# Top.net
KiCad netlist of a schematic drawn in Altium Designer
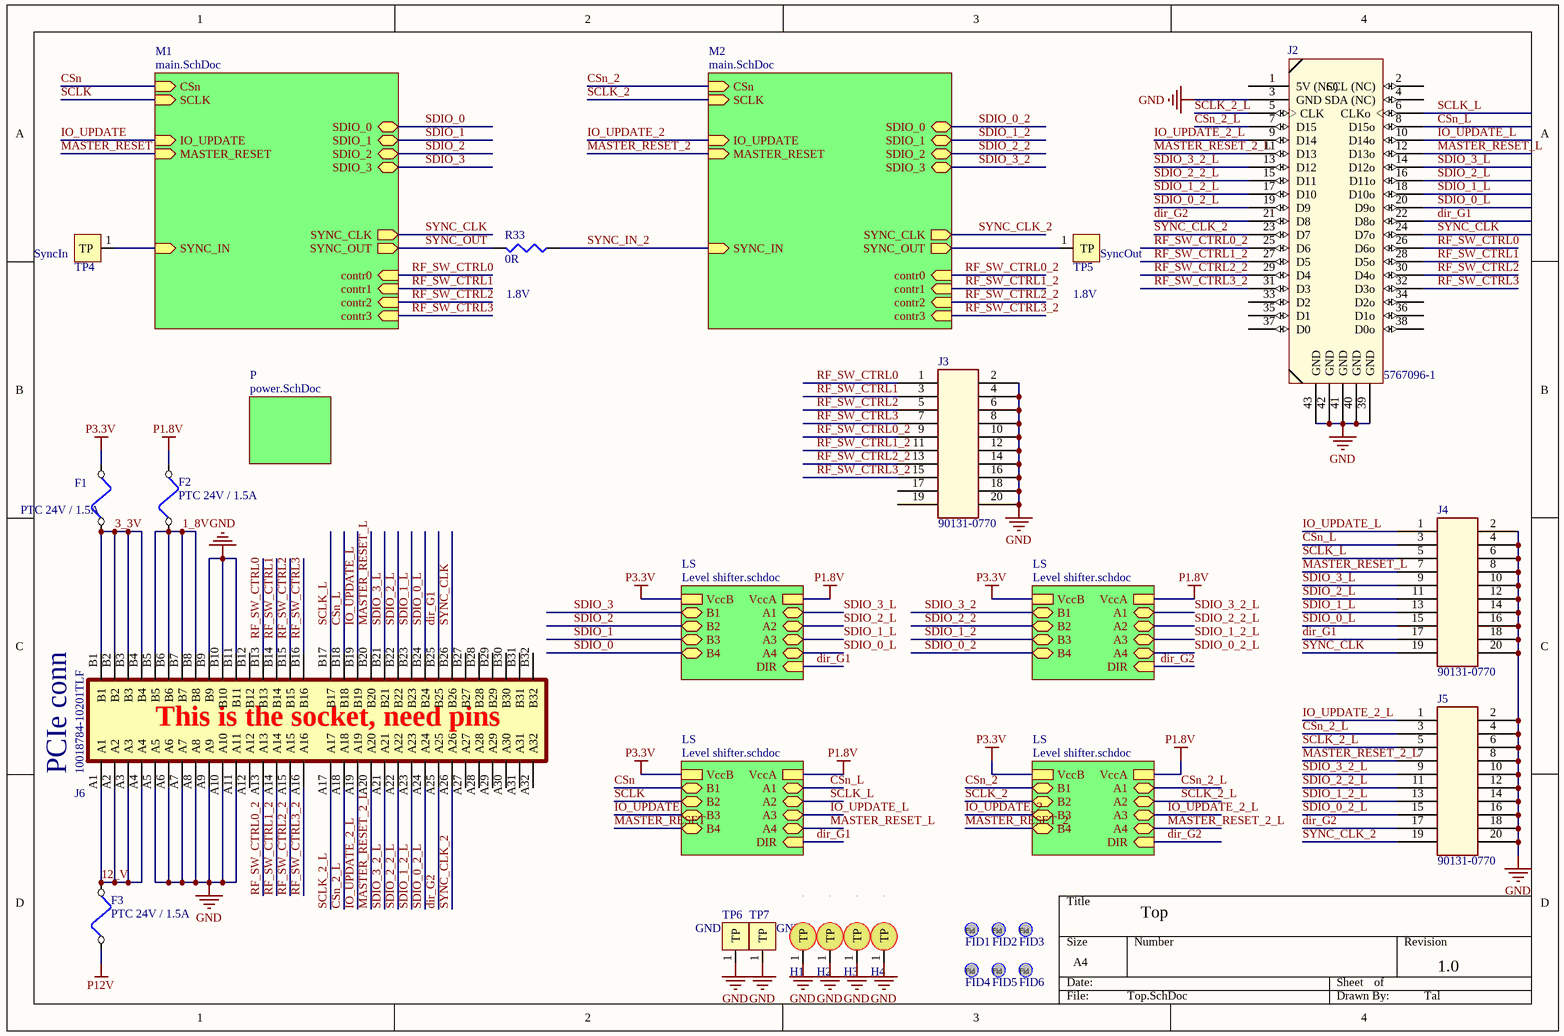
[diagram p0: Top.SchDoc]

(export (version "E")
  (design (tool "Eeschema 10.0.6"))
  (components
    (comp (ref "F1")
      (value "PTC 24V / 1.5A")
      (footprint "Landa_PCB:1812_F")
      (description "FUSE PTC 24V 1.5A POLYFUSE 1812")
      (fields
        (field (name "MANUFACTURER") "Littelfuse Inc")
        (field (name "MANUFACTURER PART NUMBER") "1812L150/24MR")
      )
      (libsource (lib "DPB_spliter") (part "1812L150/24MR"))
    )
    (comp (ref "F2")
      (value "PTC 24V / 1.5A")
      (footprint "Landa_PCB:1812_F")
      (description "FUSE PTC 24V 1.5A POLYFUSE 1812")
      (fields
        (field (name "MANUFACTURER") "Littelfuse Inc")
        (field (name "MANUFACTURER PART NUMBER") "1812L150/24MR")
      )
      (libsource (lib "DPB_spliter") (part "1812L150/24MR"))
    )
    (comp (ref "F3")
      (value "PTC 24V / 1.5A")
      (footprint "Landa_PCB:1812_F")
      (description "FUSE PTC 24V 1.5A POLYFUSE 1812")
      (fields
        (field (name "MANUFACTURER") "Littelfuse Inc")
        (field (name "MANUFACTURER PART NUMBER") "1812L150/24MR")
      )
      (libsource (lib "DPB_spliter") (part "1812L150/24MR"))
    )
    (comp (ref "FID1")
      (value "Fiducial")
      (footprint "Fiducial")
      (libsource (lib "DDS_PCB") (part "Fiducial"))
    )
    (comp (ref "FID2")
      (value "Fiducial")
      (footprint "Fiducial")
      (libsource (lib "DDS_PCB") (part "Fiducial"))
    )
    (comp (ref "FID3")
      (value "Fiducial")
      (footprint "Fiducial")
      (libsource (lib "DDS_PCB") (part "Fiducial"))
    )
    (comp (ref "FID4")
      (value "Fiducial")
      (footprint "Fiducial")
      (libsource (lib "DDS_PCB") (part "Fiducial"))
    )
    (comp (ref "FID5")
      (value "Fiducial")
      (footprint "Fiducial")
      (libsource (lib "DDS_PCB") (part "Fiducial"))
    )
    (comp (ref "FID6")
      (value "Fiducial")
      (footprint "Fiducial")
      (libsource (lib "DDS_PCB") (part "Fiducial"))
    )
    (comp (ref "H1")
      (value "Hole 3mm")
      (footprint "hole 3mm")
      (description "hole 3mm")
      (libsource (lib "L_SCH_Misc") (part "Hole 3mm"))
    )
    (comp (ref "H2")
      (value "Hole 3mm")
      (footprint "hole 3mm")
      (description "hole 3mm")
      (libsource (lib "L_SCH_Misc") (part "Hole 3mm"))
    )
    (comp (ref "H3")
      (value "Hole 3mm")
      (footprint "hole 3mm")
      (description "hole 3mm")
      (libsource (lib "L_SCH_Misc") (part "Hole 3mm"))
    )
    (comp (ref "H4")
      (value "Hole 3mm")
      (footprint "hole 3mm")
      (description "hole 3mm")
      (libsource (lib "L_SCH_Misc") (part "Hole 3mm"))
    )
    (comp (ref "J2")
      (value "5767096-1")
      (footprint "MICTOR-38_PIN")
      (description "CONN MICTOR 38POS .025 VERT SMD")
      (fields
        (field (name "MANUFACTURER") "TE Connectivity")
        (field (name "MANUFACTURER PART NUMBER") "5767096-1")
      )
      (libsource (lib "L_SCH_J_Z") (part "5767096-1"))
    )
    (comp (ref "J3")
      (value "90131-0770")
      (footprint "HEADER_10x2")
      (description "CONN HEADER 20 TH")
      (fields
        (field (name "MANUFACTURER") "Molex Connector Corporation")
        (field (name "MANUFACTURER PART NUMBER") "90131-0770")
      )
      (libsource (lib "L_SCH_J_Z") (part "90131-0770"))
    )
    (comp (ref "J4")
      (value "90131-0770")
      (footprint "HEADER_10x2")
      (description "CONN HEADER 20 TH")
      (fields
        (field (name "MANUFACTURER") "Molex Connector Corporation")
        (field (name "MANUFACTURER PART NUMBER") "90131-0770")
      )
      (libsource (lib "L_SCH_J_Z") (part "90131-0770"))
    )
    (comp (ref "J5")
      (value "90131-0770")
      (footprint "HEADER_10x2")
      (description "CONN HEADER 20 TH")
      (fields
        (field (name "MANUFACTURER") "Molex Connector Corporation")
        (field (name "MANUFACTURER PART NUMBER") "90131-0770")
      )
      (libsource (lib "L_SCH_J_Z") (part "90131-0770"))
    )
    (comp (ref "J6")
      (value "10018784-10201TLF")
      (footprint "PCIE_8LANE_EDGE")
      (description "64 Position Female Connector PCI Expressâ„¢ Gold 0.039 _1.00mm_ Black")
      (fields (field (name "MF") "Amphenol ICC"))
      (libsource (lib "10018784-10201TLF") (part "10018784-10201TLF"))
    )
    (comp (ref "R33")
      (value "0R")
      (footprint "R0402")
      (description "RES 0 OHM 1/10W 1% 0402 SMD")
      (fields
        (field (name "MANUFACTURER PART NUMBER") "ERJ-2RKF1000X")
        (field (name "MANUFACTURER") "Panasonic Electronic Components")
      )
      (libsource (lib "L_SCH_R") (part "RES 100 OHM 1/10W 1% 0402 SMD"))
    )
    (comp (ref "TP4")
      (value "SyncIn")
      (footprint "Landa_PCB:TP_2x1.8")
      (description "TP PC MINIATURE SMT")
      (fields
        (field (name "MANUFACTURER") "Keystone Electronics")
        (field (name "MANUFACTURER PART NUMBER") "5015")
      )
      (libsource (lib "DPB_spliter") (part "TP mini_2"))
    )
    (comp (ref "TP5")
      (value "SyncOut")
      (footprint "Landa_PCB:TP_2x1.8")
      (description "TP PC MINIATURE SMT")
      (fields
        (field (name "MANUFACTURER") "Keystone Electronics")
        (field (name "MANUFACTURER PART NUMBER") "5015")
      )
      (libsource (lib "") (part "TP mini_2_2"))
    )
    (comp (ref "TP6")
      (value "GND")
      (footprint "Landa_PCB:TP_2x1.8")
      (description "TP PC MINIATURE SMT")
      (fields
        (field (name "MANUFACTURER") "Keystone Electronics")
        (field (name "MANUFACTURER PART NUMBER") "5015")
      )
      (libsource (lib "") (part "TP mini_2_1"))
    )
    (comp (ref "TP7")
      (value "GND")
      (footprint "Landa_PCB:TP_2x1.8")
      (description "TP PC MINIATURE SMT")
      (fields
        (field (name "MANUFACTURER") "Keystone Electronics")
        (field (name "MANUFACTURER PART NUMBER") "5015")
      )
      (libsource (lib "DPB_spliter") (part "TP mini_1"))
    )
  )
  (nets
    (net (code "1") (name "/1_8V") (class "Default")
      (node (ref "F2") (pin "1") (pinfunction "1_1") (pintype "passive"))
      (node (ref "J6") (pin "B5") (pinfunction "B5_B5") (pintype "passive"))
      (node (ref "J6") (pin "B6") (pinfunction "B6_B6") (pintype "passive"))
      (node (ref "J6") (pin "B7") (pinfunction "B7_B7") (pintype "passive"))
      (node (ref "J6") (pin "B8") (pinfunction "B8_B8") (pintype "passive"))
    )
    (net (code "2") (name "/3_3V") (class "Default")
      (node (ref "F1") (pin "1") (pinfunction "1_1") (pintype "passive"))
      (node (ref "J6") (pin "B1") (pinfunction "B1_B1") (pintype "passive"))
      (node (ref "J6") (pin "B2") (pinfunction "B2_B2") (pintype "passive"))
      (node (ref "J6") (pin "B3") (pinfunction "B3_B3") (pintype "passive"))
      (node (ref "J6") (pin "B4") (pinfunction "B4_B4") (pintype "passive"))
    )
    (net (code "3") (name "/12_V") (class "Default")
      (node (ref "F3") (pin "2") (pinfunction "2_2") (pintype "passive"))
      (node (ref "J6") (pin "A1") (pinfunction "A1_A1") (pintype "passive"))
      (node (ref "J6") (pin "A2") (pinfunction "A2_A2") (pintype "passive"))
      (node (ref "J6") (pin "A3") (pinfunction "A3_A3") (pintype "passive"))
      (node (ref "J6") (pin "A4") (pinfunction "A4_A4") (pintype "passive"))
    )
    (net (code "6") (name "/CSn_2_L") (class "Default")
      (node (ref "J2") (pin "7") (pinfunction "D15_7") (pintype "bidirectional"))
      (node (ref "J5") (pin "3") (pinfunction "3_3") (pintype "passive"))
      (node (ref "J6") (pin "A18") (pinfunction "A18_A18") (pintype "passive"))
    )
    (net (code "7") (name "/CSn_L") (class "Default")
      (node (ref "J2") (pin "8") (pinfunction "D15o_8") (pintype "bidirectional"))
      (node (ref "J4") (pin "3") (pinfunction "3_3") (pintype "passive"))
      (node (ref "J6") (pin "B18") (pinfunction "B18_B18") (pintype "passive"))
    )
    (net (code "10") (name "/IO_UPDATE_2_L") (class "Default")
      (node (ref "J2") (pin "9") (pinfunction "D14_9") (pintype "bidirectional"))
      (node (ref "J5") (pin "1") (pinfunction "1_1") (pintype "passive"))
      (node (ref "J6") (pin "A19") (pinfunction "A19_A19") (pintype "passive"))
    )
    (net (code "11") (name "/IO_UPDATE_L") (class "Default")
      (node (ref "J2") (pin "10") (pinfunction "D14o_10") (pintype "bidirectional"))
      (node (ref "J4") (pin "1") (pinfunction "1_1") (pintype "passive"))
      (node (ref "J6") (pin "B19") (pinfunction "B19_B19") (pintype "passive"))
    )
    (net (code "14") (name "/MASTER_RESET_2_L") (class "Default")
      (node (ref "J2") (pin "11") (pinfunction "D13_11") (pintype "bidirectional"))
      (node (ref "J5") (pin "7") (pinfunction "7_7") (pintype "passive"))
      (node (ref "J6") (pin "A20") (pinfunction "A20_A20") (pintype "passive"))
    )
    (net (code "15") (name "/MASTER_RESET_L") (class "Default")
      (node (ref "J2") (pin "12") (pinfunction "D13o_12") (pintype "bidirectional"))
      (node (ref "J4") (pin "7") (pinfunction "7_7") (pintype "passive"))
      (node (ref "J6") (pin "B20") (pinfunction "B20_B20") (pintype "passive"))
    )
    (net (code "16") (name "/RF_SW_CTRL0") (class "Default")
      (node (ref "J2") (pin "26") (pinfunction "D6o_26") (pintype "bidirectional"))
      (node (ref "J3") (pin "1") (pinfunction "1_1") (pintype "passive"))
      (node (ref "J6") (pin "B13") (pinfunction "B13_B13") (pintype "passive"))
    )
    (net (code "17") (name "/RF_SW_CTRL0_2") (class "Default")
      (node (ref "J2") (pin "25") (pinfunction "D6_25") (pintype "bidirectional"))
      (node (ref "J3") (pin "9") (pinfunction "9_9") (pintype "passive"))
      (node (ref "J6") (pin "A13") (pinfunction "A13_A13") (pintype "passive"))
    )
    (net (code "18") (name "/RF_SW_CTRL1") (class "Default")
      (node (ref "J2") (pin "28") (pinfunction "D5o_28") (pintype "bidirectional"))
      (node (ref "J3") (pin "3") (pinfunction "3_3") (pintype "passive"))
      (node (ref "J6") (pin "B14") (pinfunction "B14_B14") (pintype "passive"))
    )
    (net (code "19") (name "/RF_SW_CTRL1_2") (class "Default")
      (node (ref "J2") (pin "27") (pinfunction "D5_27") (pintype "bidirectional"))
      (node (ref "J3") (pin "11") (pinfunction "11_11") (pintype "passive"))
      (node (ref "J6") (pin "A14") (pinfunction "A14_A14") (pintype "passive"))
    )
    (net (code "20") (name "/RF_SW_CTRL2") (class "Default")
      (node (ref "J2") (pin "30") (pinfunction "D4o_30") (pintype "bidirectional"))
      (node (ref "J3") (pin "5") (pinfunction "5_5") (pintype "passive"))
      (node (ref "J6") (pin "B15") (pinfunction "B15_B15") (pintype "passive"))
    )
    (net (code "21") (name "/RF_SW_CTRL2_2") (class "Default")
      (node (ref "J2") (pin "29") (pinfunction "D4_29") (pintype "bidirectional"))
      (node (ref "J3") (pin "13") (pinfunction "13_13") (pintype "passive"))
      (node (ref "J6") (pin "A15") (pinfunction "A15_A15") (pintype "passive"))
    )
    (net (code "22") (name "/RF_SW_CTRL3") (class "Default")
      (node (ref "J2") (pin "32") (pinfunction "D3o_32") (pintype "bidirectional"))
      (node (ref "J3") (pin "7") (pinfunction "7_7") (pintype "passive"))
      (node (ref "J6") (pin "B16") (pinfunction "B16_B16") (pintype "passive"))
    )
    (net (code "23") (name "/RF_SW_CTRL3_2") (class "Default")
      (node (ref "J2") (pin "31") (pinfunction "D3_31") (pintype "bidirectional"))
      (node (ref "J3") (pin "15") (pinfunction "15_15") (pintype "passive"))
      (node (ref "J6") (pin "A16") (pinfunction "A16_A16") (pintype "passive"))
    )
    (net (code "26") (name "/SCLK_2_L") (class "Default")
      (node (ref "J2") (pin "5") (pinfunction "CLK_5") (pintype "bidirectional"))
      (node (ref "J5") (pin "5") (pinfunction "5_5") (pintype "passive"))
      (node (ref "J6") (pin "A17") (pinfunction "A17_A17") (pintype "passive"))
    )
    (net (code "27") (name "/SCLK_L") (class "Default")
      (node (ref "J2") (pin "6") (pinfunction "CLKo_6") (pintype "bidirectional"))
      (node (ref "J4") (pin "5") (pinfunction "5_5") (pintype "passive"))
      (node (ref "J6") (pin "B17") (pinfunction "B17_B17") (pintype "passive"))
    )
    (net (code "30") (name "/SDIO_0_2_L") (class "Default")
      (node (ref "J2") (pin "19") (pinfunction "D9_19") (pintype "bidirectional"))
      (node (ref "J5") (pin "15") (pinfunction "15_15") (pintype "passive"))
      (node (ref "J6") (pin "A24") (pinfunction "A24_A24") (pintype "passive"))
    )
    (net (code "31") (name "/SDIO_0_L") (class "Default")
      (node (ref "J2") (pin "20") (pinfunction "D9o_20") (pintype "bidirectional"))
      (node (ref "J4") (pin "15") (pinfunction "15_15") (pintype "passive"))
      (node (ref "J6") (pin "B24") (pinfunction "B24_B24") (pintype "passive"))
    )
    (net (code "34") (name "/SDIO_1_2_L") (class "Default")
      (node (ref "J2") (pin "17") (pinfunction "D10_17") (pintype "bidirectional"))
      (node (ref "J5") (pin "13") (pinfunction "13_13") (pintype "passive"))
      (node (ref "J6") (pin "A23") (pinfunction "A23_A23") (pintype "passive"))
    )
    (net (code "35") (name "/SDIO_1_L") (class "Default")
      (node (ref "J2") (pin "18") (pinfunction "D10o_18") (pintype "bidirectional"))
      (node (ref "J4") (pin "13") (pinfunction "13_13") (pintype "passive"))
      (node (ref "J6") (pin "B23") (pinfunction "B23_B23") (pintype "passive"))
    )
    (net (code "38") (name "/SDIO_2_2_L") (class "Default")
      (node (ref "J2") (pin "15") (pinfunction "D11_15") (pintype "bidirectional"))
      (node (ref "J5") (pin "11") (pinfunction "11_11") (pintype "passive"))
      (node (ref "J6") (pin "A22") (pinfunction "A22_A22") (pintype "passive"))
    )
    (net (code "39") (name "/SDIO_2_L") (class "Default")
      (node (ref "J2") (pin "16") (pinfunction "D11o_16") (pintype "bidirectional"))
      (node (ref "J4") (pin "11") (pinfunction "11_11") (pintype "passive"))
      (node (ref "J6") (pin "B22") (pinfunction "B22_B22") (pintype "passive"))
    )
    (net (code "42") (name "/SDIO_3_2_L") (class "Default")
      (node (ref "J2") (pin "13") (pinfunction "D12_13") (pintype "bidirectional"))
      (node (ref "J5") (pin "9") (pinfunction "9_9") (pintype "passive"))
      (node (ref "J6") (pin "A21") (pinfunction "A21_A21") (pintype "passive"))
    )
    (net (code "43") (name "/SDIO_3_L") (class "Default")
      (node (ref "J2") (pin "14") (pinfunction "D12o_14") (pintype "bidirectional"))
      (node (ref "J4") (pin "9") (pinfunction "9_9") (pintype "passive"))
      (node (ref "J6") (pin "B21") (pinfunction "B21_B21") (pintype "passive"))
    )
    (net (code "44") (name "/SYNC_CLK") (class "Default")
      (node (ref "J2") (pin "24") (pinfunction "D7o_24") (pintype "bidirectional"))
      (node (ref "J4") (pin "19") (pinfunction "19_19") (pintype "passive"))
      (node (ref "J6") (pin "B26") (pinfunction "B26_B26") (pintype "passive"))
    )
    (net (code "45") (name "/SYNC_CLK_2") (class "Default")
      (node (ref "J2") (pin "23") (pinfunction "D7_23") (pintype "bidirectional"))
      (node (ref "J5") (pin "19") (pinfunction "19_19") (pintype "passive"))
      (node (ref "J6") (pin "A26") (pinfunction "A26_A26") (pintype "passive"))
    )
    (net (code "46") (name "/SYNC_IN") (class "Default")
      (node (ref "TP4") (pin "1") (pinfunction "TP_1") (pintype "passive"))
    )
    (net (code "47") (name "/SYNC_IN_2") (class "Default")
      (node (ref "R33") (pin "1") (pinfunction "1_1") (pintype "passive"))
    )
    (net (code "48") (name "/SYNC_OUT") (class "Default")
      (node (ref "R33") (pin "2") (pinfunction "2_2") (pintype "passive"))
    )
    (net (code "49") (name "/SYNC_OUT_1") (class "Default")
      (node (ref "TP5") (pin "1") (pinfunction "TP_1") (pintype "passive"))
    )
    (net (code "50") (name "/dir_G1") (class "Default")
      (node (ref "J2") (pin "22") (pinfunction "D8o_22") (pintype "bidirectional"))
      (node (ref "J4") (pin "17") (pinfunction "17_17") (pintype "passive"))
      (node (ref "J6") (pin "B25") (pinfunction "B25_B25") (pintype "passive"))
    )
    (net (code "51") (name "/dir_G2") (class "Default")
      (node (ref "J2") (pin "21") (pinfunction "D8_21") (pintype "bidirectional"))
      (node (ref "J5") (pin "17") (pinfunction "17_17") (pintype "passive"))
      (node (ref "J6") (pin "A25") (pinfunction "A25_A25") (pintype "passive"))
    )
    (net (code "52") (name "GND") (class "Default")
      (node (ref "H1") (pin "1") (pinfunction "TP_1") (pintype "passive"))
      (node (ref "H2") (pin "1") (pinfunction "TP_1") (pintype "passive"))
      (node (ref "H3") (pin "1") (pinfunction "TP_1") (pintype "passive"))
      (node (ref "H4") (pin "1") (pinfunction "TP_1") (pintype "passive"))
      (node (ref "J2") (pin "3") (pinfunction "GND_3") (pintype "power_in"))
      (node (ref "J2") (pin "39") (pinfunction "GND_39") (pintype "power_in"))
      (node (ref "J2") (pin "40") (pinfunction "GND_40") (pintype "power_in"))
      (node (ref "J2") (pin "41") (pinfunction "GND_41") (pintype "power_in"))
      (node (ref "J2") (pin "42") (pinfunction "GND_42") (pintype "power_in"))
      (node (ref "J2") (pin "43") (pinfunction "GND_43") (pintype "power_in"))
      (node (ref "J3") (pin "10") (pinfunction "10_10") (pintype "passive"))
      (node (ref "J3") (pin "12") (pinfunction "12_12") (pintype "passive"))
      (node (ref "J3") (pin "14") (pinfunction "14_14") (pintype "passive"))
      (node (ref "J3") (pin "16") (pinfunction "16_16") (pintype "passive"))
      (node (ref "J3") (pin "18") (pinfunction "18_18") (pintype "passive"))
      (node (ref "J3") (pin "2") (pinfunction "2_2") (pintype "passive"))
      (node (ref "J3") (pin "20") (pinfunction "20_20") (pintype "passive"))
      (node (ref "J3") (pin "4") (pinfunction "4_4") (pintype "passive"))
      (node (ref "J3") (pin "6") (pinfunction "6_6") (pintype "passive"))
      (node (ref "J3") (pin "8") (pinfunction "8_8") (pintype "passive"))
      (node (ref "J4") (pin "10") (pinfunction "10_10") (pintype "passive"))
      (node (ref "J4") (pin "12") (pinfunction "12_12") (pintype "passive"))
      (node (ref "J4") (pin "14") (pinfunction "14_14") (pintype "passive"))
      (node (ref "J4") (pin "16") (pinfunction "16_16") (pintype "passive"))
      (node (ref "J4") (pin "18") (pinfunction "18_18") (pintype "passive"))
      (node (ref "J4") (pin "2") (pinfunction "2_2") (pintype "passive"))
      (node (ref "J4") (pin "20") (pinfunction "20_20") (pintype "passive"))
      (node (ref "J4") (pin "4") (pinfunction "4_4") (pintype "passive"))
      (node (ref "J4") (pin "6") (pinfunction "6_6") (pintype "passive"))
      (node (ref "J4") (pin "8") (pinfunction "8_8") (pintype "passive"))
      (node (ref "J5") (pin "10") (pinfunction "10_10") (pintype "passive"))
      (node (ref "J5") (pin "12") (pinfunction "12_12") (pintype "passive"))
      (node (ref "J5") (pin "14") (pinfunction "14_14") (pintype "passive"))
      (node (ref "J5") (pin "16") (pinfunction "16_16") (pintype "passive"))
      (node (ref "J5") (pin "18") (pinfunction "18_18") (pintype "passive"))
      (node (ref "J5") (pin "2") (pinfunction "2_2") (pintype "passive"))
      (node (ref "J5") (pin "20") (pinfunction "20_20") (pintype "passive"))
      (node (ref "J5") (pin "4") (pinfunction "4_4") (pintype "passive"))
      (node (ref "J5") (pin "6") (pinfunction "6_6") (pintype "passive"))
      (node (ref "J5") (pin "8") (pinfunction "8_8") (pintype "passive"))
      (node (ref "J6") (pin "A10") (pinfunction "A10_A10") (pintype "passive"))
      (node (ref "J6") (pin "A11") (pinfunction "A11_A11") (pintype "passive"))
      (node (ref "J6") (pin "A5") (pinfunction "A5_A5") (pintype "passive"))
      (node (ref "J6") (pin "A6") (pinfunction "A6_A6") (pintype "passive"))
      (node (ref "J6") (pin "A7") (pinfunction "A7_A7") (pintype "passive"))
      (node (ref "J6") (pin "A8") (pinfunction "A8_A8") (pintype "passive"))
      (node (ref "J6") (pin "A9") (pinfunction "A9_A9") (pintype "passive"))
      (node (ref "J6") (pin "B10") (pinfunction "B10_B10") (pintype "passive"))
      (node (ref "J6") (pin "B11") (pinfunction "B11_B11") (pintype "passive"))
      (node (ref "J6") (pin "B9") (pinfunction "B9_B9") (pintype "passive"))
      (node (ref "TP6") (pin "1") (pinfunction "TP_1") (pintype "passive"))
      (node (ref "TP7") (pin "1") (pinfunction "TP_1") (pintype "passive"))
    )
    (net (code "53") (name "P1.8V") (class "Default")
      (node (ref "F2") (pin "2") (pinfunction "2_2") (pintype "passive"))
    )
    (net (code "54") (name "P3.3V") (class "Default")
      (node (ref "F1") (pin "2") (pinfunction "2_2") (pintype "passive"))
    )
    (net (code "55") (name "P12V") (class "Default")
      (node (ref "F3") (pin "1") (pinfunction "1_1") (pintype "passive"))
    )
    (net (code "56") (name "unconnected-(J2-5V_(NC)-Pad1)") (class "Default")
      (node (ref "J2") (pin "1") (pinfunction "5V_(NC)_1") (pintype "power_in"))
    )
    (net (code "57") (name "unconnected-(J2-D0-Pad37)") (class "Default")
      (node (ref "J2") (pin "37") (pinfunction "D0_37") (pintype "bidirectional"))
    )
    (net (code "58") (name "unconnected-(J2-D0o-Pad38)") (class "Default")
      (node (ref "J2") (pin "38") (pinfunction "D0o_38") (pintype "bidirectional"))
    )
    (net (code "59") (name "unconnected-(J2-D1-Pad35)") (class "Default")
      (node (ref "J2") (pin "35") (pinfunction "D1_35") (pintype "bidirectional"))
    )
    (net (code "60") (name "unconnected-(J2-D1o-Pad36)") (class "Default")
      (node (ref "J2") (pin "36") (pinfunction "D1o_36") (pintype "bidirectional"))
    )
    (net (code "61") (name "unconnected-(J2-D2-Pad33)") (class "Default")
      (node (ref "J2") (pin "33") (pinfunction "D2_33") (pintype "bidirectional"))
    )
    (net (code "62") (name "unconnected-(J2-D2o-Pad34)") (class "Default")
      (node (ref "J2") (pin "34") (pinfunction "D2o_34") (pintype "bidirectional"))
    )
    (net (code "63") (name "unconnected-(J2-SCL_(NC)-Pad2)") (class "Default")
      (node (ref "J2") (pin "2") (pinfunction "SCL_(NC)_2") (pintype "bidirectional"))
    )
    (net (code "64") (name "unconnected-(J2-SDA_(NC)-Pad4)") (class "Default")
      (node (ref "J2") (pin "4") (pinfunction "SDA_(NC)_4") (pintype "bidirectional"))
    )
    (net (code "65") (name "unconnected-(J3-Pad17)") (class "Default")
      (node (ref "J3") (pin "17") (pinfunction "17_17") (pintype "passive"))
    )
    (net (code "66") (name "unconnected-(J3-Pad19)") (class "Default")
      (node (ref "J3") (pin "19") (pinfunction "19_19") (pintype "passive"))
    )
    (net (code "67") (name "unconnected-(J6-PadA12)") (class "Default")
      (node (ref "J6") (pin "A12") (pinfunction "A12_A12") (pintype "passive"))
    )
    (net (code "68") (name "unconnected-(J6-PadA27)") (class "Default")
      (node (ref "J6") (pin "A27") (pinfunction "A27_A27") (pintype "passive"))
    )
    (net (code "69") (name "unconnected-(J6-PadA28)") (class "Default")
      (node (ref "J6") (pin "A28") (pinfunction "A28_A28") (pintype "passive"))
    )
    (net (code "70") (name "unconnected-(J6-PadA29)") (class "Default")
      (node (ref "J6") (pin "A29") (pinfunction "A29_A29") (pintype "passive"))
    )
    (net (code "71") (name "unconnected-(J6-PadA30)") (class "Default")
      (node (ref "J6") (pin "A30") (pinfunction "A30_A30") (pintype "passive"))
    )
    (net (code "72") (name "unconnected-(J6-PadA31)") (class "Default")
      (node (ref "J6") (pin "A31") (pinfunction "A31_A31") (pintype "passive"))
    )
    (net (code "73") (name "unconnected-(J6-PadA32)") (class "Default")
      (node (ref "J6") (pin "A32") (pinfunction "A32_A32") (pintype "passive"))
    )
    (net (code "74") (name "unconnected-(J6-PadB12)") (class "Default")
      (node (ref "J6") (pin "B12") (pinfunction "B12_B12") (pintype "passive"))
    )
    (net (code "75") (name "unconnected-(J6-PadB27)") (class "Default")
      (node (ref "J6") (pin "B27") (pinfunction "B27_B27") (pintype "passive"))
    )
    (net (code "76") (name "unconnected-(J6-PadB28)") (class "Default")
      (node (ref "J6") (pin "B28") (pinfunction "B28_B28") (pintype "passive"))
    )
    (net (code "77") (name "unconnected-(J6-PadB29)") (class "Default")
      (node (ref "J6") (pin "B29") (pinfunction "B29_B29") (pintype "passive"))
    )
    (net (code "78") (name "unconnected-(J6-PadB30)") (class "Default")
      (node (ref "J6") (pin "B30") (pinfunction "B30_B30") (pintype "passive"))
    )
    (net (code "79") (name "unconnected-(J6-PadB31)") (class "Default")
      (node (ref "J6") (pin "B31") (pinfunction "B31_B31") (pintype "passive"))
    )
    (net (code "80") (name "unconnected-(J6-PadB32)") (class "Default")
      (node (ref "J6") (pin "B32") (pinfunction "B32_B32") (pintype "passive"))
    )
  )
)
